# Sensor.net
KiCad netlist of a schematic drawn in Altium Designer
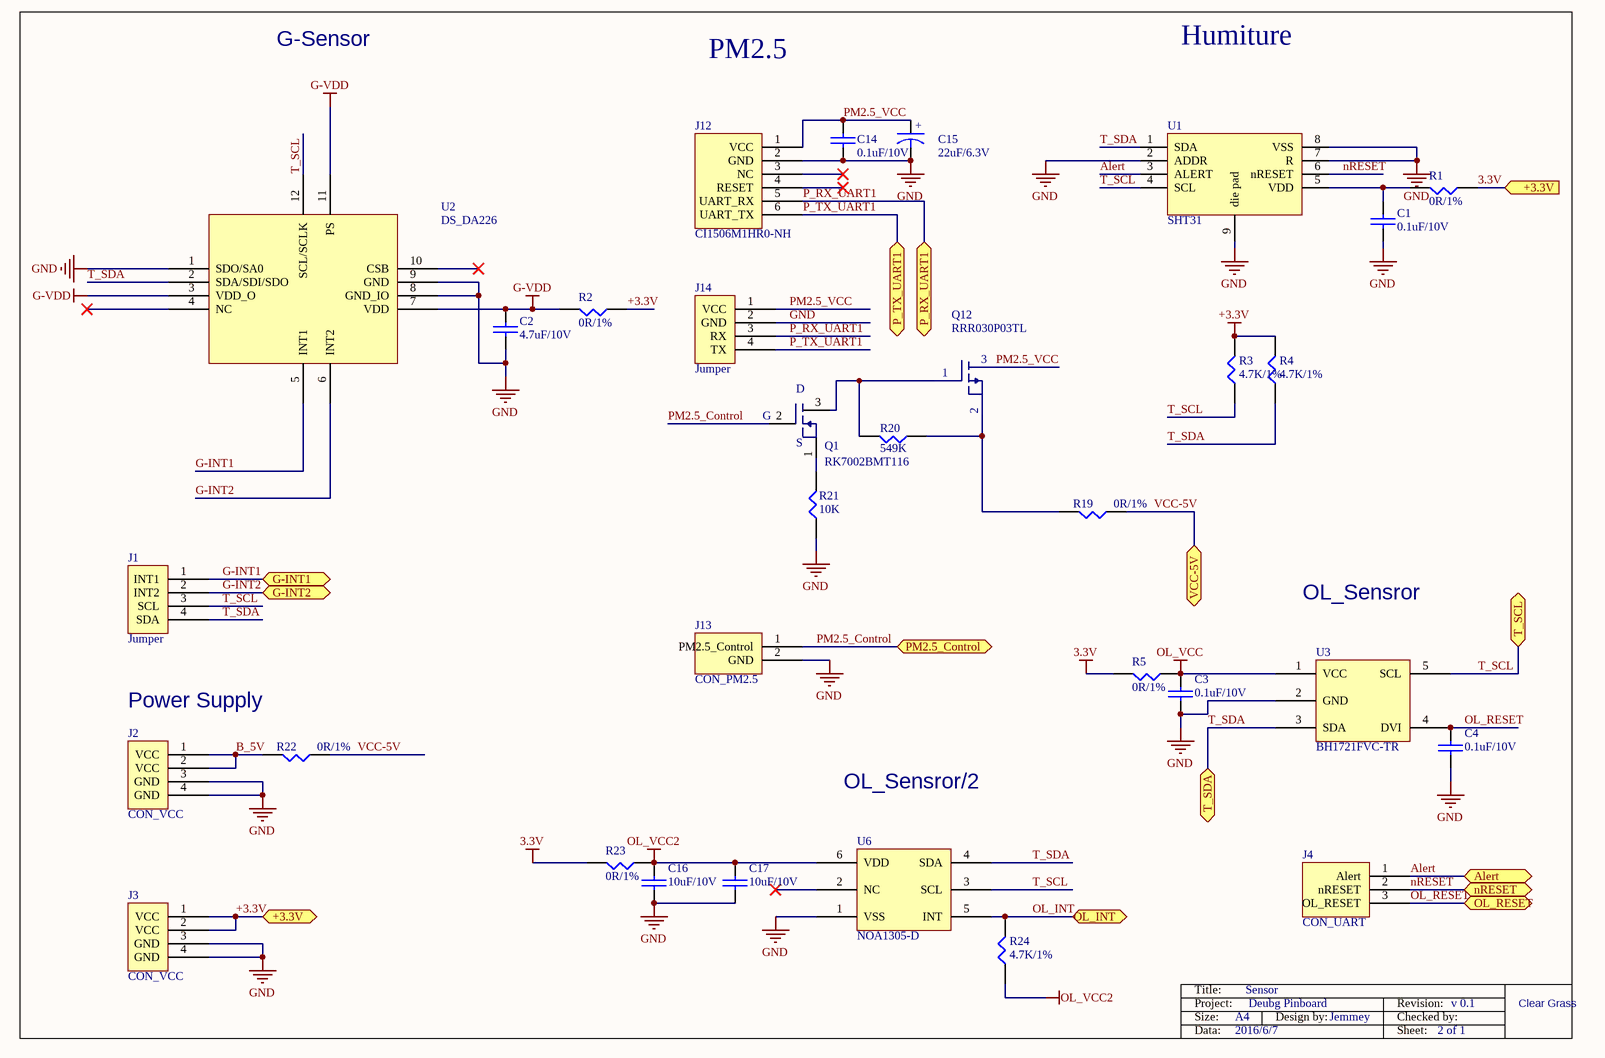
[diagram p0: Sensor.SchDoc]

(export (version "E")
  (design (tool "Eeschema 10.0.6"))
  (components
    (comp (ref "C1")
      (value "0.1uF/10V")
      (footprint "0402C")
      (description "厂家：Murata，型号：GRM155R71A104KA01D")
      (libsource (lib "*") (part "CAP"))
    )
    (comp (ref "C2")
      (value "4.7uF/10V")
      (footprint "0402C")
      (description "厂家：Murata，型号：GRM155R71A104KA01D")
      (libsource (lib "*") (part "CAP"))
    )
    (comp (ref "C3")
      (value "0.1uF/10V")
      (footprint "0402C")
      (description "厂家：Murata，型号：")
      (libsource (lib "*") (part "CAP"))
    )
    (comp (ref "C4")
      (value "0.1uF/10V")
      (footprint "0402C")
      (description "厂家：Murata，型号：")
      (libsource (lib "*") (part "CAP"))
    )
    (comp (ref "C14")
      (value "0.1uF/10V")
      (footprint "0402C")
      (description "厂家：Murata，型号：")
      (libsource (lib "*") (part "CAP"))
    )
    (comp (ref "C15")
      (value "22uF/6.3V")
      (footprint "3216")
      (description "厂家：ROHM，型号：TAJC227K010RNJ")
      (libsource (lib "MoJi LIB") (part "Capacitor"))
    )
    (comp (ref "C16")
      (value "10uF/10V")
      (footprint "0603C")
      (description "厂家：Murata，型号：")
      (libsource (lib "*") (part "CAP"))
    )
    (comp (ref "C17")
      (value "10uF/10V")
      (footprint "0603C")
      (description "厂家：Murata，型号：")
      (libsource (lib "*") (part "CAP"))
    )
    (comp (ref "J1")
      (value "Jumper")
      (footprint "2.54*4")
      (libsource (lib "Debug Pinborad_1") (part "Jumper*4"))
    )
    (comp (ref "J2")
      (value "CON_VCC")
      (footprint "2.54*4")
      (libsource (lib "Debug Pinborad_1") (part "CON_VCC"))
    )
    (comp (ref "J3")
      (value "CON_VCC")
      (footprint "2.54*4")
      (libsource (lib "Debug Pinborad_1") (part "CON_VCC"))
    )
    (comp (ref "J4")
      (value "CON_UART")
      (footprint "2.54*3")
      (libsource (lib "Debug Pinborad") (part "CON_UART"))
    )
    (comp (ref "J12")
      (value "CI1506M1HR0-NH")
      (footprint "WTB_SIDE_6PIN")
      (description "厂家：瀚荃股份，型号：CI1506M1HR0-NH")
      (libsource (lib "Bran PinBoard") (part "CI1506M1HR0-NH"))
    )
    (comp (ref "J13")
      (value "CON_PM2.5")
      (footprint "2.54*2")
      (libsource (lib "Bran PinBoard") (part "CON_PM2.5"))
    )
    (comp (ref "J14")
      (value "Jumper")
      (footprint "2.54*4")
      (libsource (lib "Bran PinBoard") (part "Jumper*4*PM25"))
    )
    (comp (ref "Q1")
      (value "RK7002BMT116")
      (footprint "SOT23")
      (description "厂家：ROHM，型号：RK7002BMT116")
      (libsource (lib "Amber") (part "RK7002BMT116"))
    )
    (comp (ref "Q12")
      (value "RRR030P03TL")
      (footprint "TSMT3")
      (description "厂家：ROHM，型号：RRR030P03TL")
      (libsource (lib "*") (part "PMOS"))
    )
    (comp (ref "R1")
      (value "0R/1%")
      (footprint "0603R")
      (description "厂家：Yageo，型号：RC0402FR-0710KL")
      (libsource (lib "*") (part "RES1"))
    )
    (comp (ref "R2")
      (value "0R/1%")
      (footprint "0603R")
      (description "厂家：Yageo，型号：RC0402FR-0710KL")
      (libsource (lib "*") (part "RES1"))
    )
    (comp (ref "R3")
      (value "4.7K/1%")
      (footprint "0402R")
      (description "厂家：Yageo，型号：RC0402FR-0710KL")
      (libsource (lib "*") (part "RES1"))
    )
    (comp (ref "R4")
      (value "4.7K/1%")
      (footprint "0402R")
      (description "厂家：Yageo，型号：RC0402FR-0710KL")
      (libsource (lib "*") (part "RES1"))
    )
    (comp (ref "R5")
      (value "0R/1%")
      (footprint "0603R")
      (description "厂家：Yageo，型号：RC0402FR-0710KL")
      (libsource (lib "*") (part "RES1"))
    )
    (comp (ref "R19")
      (value "0R/1%")
      (footprint "0603R")
      (description "厂家：Yageo，型号：RC0402FR-070RL")
      (libsource (lib "*") (part "RES1"))
    )
    (comp (ref "R20") (value "549K") (footprint "0402R") (libsource (lib "*") (part "RES1")))
    (comp (ref "R21") (value "10K") (footprint "0402R") (libsource (lib "*") (part "RES1")))
    (comp (ref "R22")
      (value "0R/1%")
      (footprint "0603R")
      (description "厂家：Yageo，型号：RC0402FR-070RL")
      (libsource (lib "*") (part "RES1"))
    )
    (comp (ref "R23")
      (value "0R/1%")
      (footprint "0603R")
      (description "厂家：Yageo，型号：RC0402FR-0710KL")
      (libsource (lib "*") (part "RES1"))
    )
    (comp (ref "R24")
      (value "4.7K/1%")
      (footprint "0402R")
      (description "厂家：Yageo，型号：RC0402FR-0710KL")
      (libsource (lib "*") (part "RES1"))
    )
    (comp (ref "U1")
      (value "SHT31")
      (footprint "DFN")
      (description "厂家：盛思睿，型号：SHT31")
      (libsource (lib "Temp Sensirion assy FPC") (part "SHT31"))
    )
    (comp (ref "U2")
      (value "DS_DA226")
      (footprint "LGA-12")
      (description "厂家：ST，型号：LIS2DH12")
      (libsource (lib "Debug Pinborad") (part "LIS2DE12"))
    )
    (comp (ref "U3")
      (value "BH1721FVC-TR")
      (footprint "WSOF5")
      (libsource (lib "Schlib1") (part "BH1721FVC-TR"))
    )
    (comp (ref "U6")
      (value "NOA1305-D")
      (footprint "CUDFN6")
      (libsource (lib "Bran PinBoard") (part "NOA1305-D"))
    )
  )
  (nets
    (net (code "1") (name "+3.3V") (class "Default")
      (node (ref "J3") (pin "1") (pinfunction "VCC_1") (pintype "passive"))
      (node (ref "J3") (pin "2") (pinfunction "VCC_2") (pintype "passive"))
      (node (ref "R1") (pin "1") (pinfunction "1_1") (pintype "passive"))
      (node (ref "R2") (pin "1") (pinfunction "1_1") (pintype "passive"))
      (node (ref "R23") (pin "2") (pinfunction "2_2") (pintype "passive"))
      (node (ref "R3") (pin "2") (pinfunction "2_2") (pintype "passive"))
      (node (ref "R4") (pin "2") (pinfunction "2_2") (pintype "passive"))
      (node (ref "R5") (pin "2") (pinfunction "2_2") (pintype "passive"))
    )
    (net (code "2") (name "/Alert") (class "Default")
      (node (ref "J4") (pin "1") (pinfunction "Alert_1") (pintype "passive"))
      (node (ref "U1") (pin "3") (pinfunction "ALERT_3") (pintype "passive"))
    )
    (net (code "3") (name "/B_5V") (class "Default")
      (node (ref "J2") (pin "1") (pinfunction "VCC_1") (pintype "passive"))
      (node (ref "J2") (pin "2") (pinfunction "VCC_2") (pintype "passive"))
      (node (ref "R22") (pin "2") (pinfunction "2_2") (pintype "passive"))
    )
    (net (code "4") (name "/G-INT1") (class "Default")
      (node (ref "J1") (pin "1") (pinfunction "INT1_1") (pintype "passive"))
      (node (ref "U2") (pin "5") (pinfunction "INT1_5") (pintype "passive"))
    )
    (net (code "5") (name "/G-INT2") (class "Default")
      (node (ref "J1") (pin "2") (pinfunction "INT2_2") (pintype "passive"))
      (node (ref "U2") (pin "6") (pinfunction "INT2_6") (pintype "passive"))
    )
    (net (code "6") (name "/OL_INT") (class "Default")
      (node (ref "R24") (pin "2") (pinfunction "2_2") (pintype "passive"))
      (node (ref "U6") (pin "5") (pinfunction "INT_5") (pintype "passive"))
    )
    (net (code "7") (name "/OL_RESET") (class "Default")
      (node (ref "C4") (pin "1") (pinfunction "1_1") (pintype "passive"))
      (node (ref "J4") (pin "3") (pinfunction "OL_RESET_3") (pintype "passive"))
      (node (ref "U3") (pin "4") (pinfunction "DVI_4") (pintype "passive"))
    )
    (net (code "8") (name "/PM2.5_Control") (class "Default")
      (node (ref "J13") (pin "1") (pinfunction "PM2.5_Control_1") (pintype "passive"))
      (node (ref "Q1") (pin "2") (pinfunction "G_2") (pintype "passive"))
    )
    (net (code "9") (name "/PM2.5_VCC") (class "Default")
      (node (ref "C14") (pin "1") (pinfunction "1_1") (pintype "passive"))
      (node (ref "C15") (pin "1") (pinfunction "1_1") (pintype "passive"))
      (node (ref "J12") (pin "1") (pinfunction "VCC_1") (pintype "passive"))
      (node (ref "J14") (pin "1") (pinfunction "VCC_1") (pintype "passive"))
      (node (ref "Q12") (pin "3") (pinfunction "D_3") (pintype "passive"))
    )
    (net (code "10") (name "/P_RX_UART1") (class "Default")
      (node (ref "J12") (pin "5") (pinfunction "UART_RX_5") (pintype "passive"))
      (node (ref "J14") (pin "3") (pinfunction "RX_3") (pintype "passive"))
    )
    (net (code "11") (name "/P_TX_UART1") (class "Default")
      (node (ref "J12") (pin "6") (pinfunction "UART_TX_6") (pintype "passive"))
      (node (ref "J14") (pin "4") (pinfunction "TX_4") (pintype "passive"))
    )
    (net (code "12") (name "/T_SCL") (class "Default")
      (node (ref "J1") (pin "3") (pinfunction "SCL_3") (pintype "passive"))
      (node (ref "R3") (pin "1") (pinfunction "1_1") (pintype "passive"))
      (node (ref "U1") (pin "4") (pinfunction "SCL_4") (pintype "passive"))
      (node (ref "U2") (pin "12") (pinfunction "SCL/SCLK_12") (pintype "passive"))
      (node (ref "U3") (pin "5") (pinfunction "SCL_5") (pintype "passive"))
      (node (ref "U6") (pin "3") (pinfunction "SCL_3") (pintype "passive"))
    )
    (net (code "13") (name "/T_SDA") (class "Default")
      (node (ref "J1") (pin "4") (pinfunction "SDA_4") (pintype "passive"))
      (node (ref "R4") (pin "1") (pinfunction "1_1") (pintype "passive"))
      (node (ref "U1") (pin "1") (pinfunction "SDA_1") (pintype "passive"))
      (node (ref "U2") (pin "2") (pinfunction "SDA/SDI/SDO_2") (pintype "passive"))
      (node (ref "U3") (pin "3") (pinfunction "SDA_3") (pintype "passive"))
      (node (ref "U6") (pin "4") (pinfunction "SDA_4") (pintype "passive"))
    )
    (net (code "14") (name "/VCC-5V") (class "Default")
      (node (ref "R19") (pin "1") (pinfunction "1_1") (pintype "passive"))
      (node (ref "R22") (pin "1") (pinfunction "1_1") (pintype "passive"))
    )
    (net (code "15") (name "/nRESET") (class "Default")
      (node (ref "J4") (pin "2") (pinfunction "nRESET_2") (pintype "passive"))
      (node (ref "U1") (pin "6") (pinfunction "nRESET_6") (pintype "passive"))
    )
    (net (code "16") (name "G-VDD") (class "Default")
      (node (ref "C2") (pin "1") (pinfunction "1_1") (pintype "passive"))
      (node (ref "R2") (pin "2") (pinfunction "2_2") (pintype "passive"))
      (node (ref "U2") (pin "11") (pinfunction "PS_11") (pintype "passive"))
      (node (ref "U2") (pin "3") (pinfunction "VDD_O_3") (pintype "passive"))
      (node (ref "U2") (pin "7") (pinfunction "VDD_7") (pintype "passive"))
    )
    (net (code "17") (name "GND") (class "Default")
      (node (ref "C1") (pin "2") (pinfunction "2_2") (pintype "passive"))
      (node (ref "C14") (pin "2") (pinfunction "2_2") (pintype "passive"))
      (node (ref "C15") (pin "2") (pinfunction "2_2") (pintype "passive"))
      (node (ref "C16") (pin "2") (pinfunction "2_2") (pintype "passive"))
      (node (ref "C17") (pin "2") (pinfunction "2_2") (pintype "passive"))
      (node (ref "C2") (pin "2") (pinfunction "2_2") (pintype "passive"))
      (node (ref "C3") (pin "2") (pinfunction "2_2") (pintype "passive"))
      (node (ref "C4") (pin "2") (pinfunction "2_2") (pintype "passive"))
      (node (ref "J12") (pin "2") (pinfunction "GND_2") (pintype "passive"))
      (node (ref "J13") (pin "2") (pinfunction "GND_2") (pintype "passive"))
      (node (ref "J14") (pin "2") (pinfunction "GND_2") (pintype "passive"))
      (node (ref "J2") (pin "3") (pinfunction "GND_3") (pintype "passive"))
      (node (ref "J2") (pin "4") (pinfunction "GND_4") (pintype "passive"))
      (node (ref "J3") (pin "3") (pinfunction "GND_3") (pintype "passive"))
      (node (ref "J3") (pin "4") (pinfunction "GND_4") (pintype "passive"))
      (node (ref "R21") (pin "1") (pinfunction "1_1") (pintype "passive"))
      (node (ref "U1") (pin "2") (pinfunction "ADDR_2") (pintype "passive"))
      (node (ref "U1") (pin "7") (pinfunction "R_7") (pintype "passive"))
      (node (ref "U1") (pin "8") (pinfunction "VSS_8") (pintype "passive"))
      (node (ref "U1") (pin "9") (pinfunction "die_pad_9") (pintype "passive"))
      (node (ref "U2") (pin "1") (pinfunction "SDO/SA0_1") (pintype "passive"))
      (node (ref "U2") (pin "8") (pinfunction "GND_IO_8") (pintype "passive"))
      (node (ref "U2") (pin "9") (pinfunction "GND_9") (pintype "passive"))
      (node (ref "U3") (pin "2") (pinfunction "GND_2") (pintype "passive"))
      (node (ref "U6") (pin "1") (pinfunction "VSS_1") (pintype "passive"))
    )
    (net (code "18") (name "Net-(Q1-D)") (class "Default")
      (node (ref "Q1") (pin "3") (pinfunction "D_3") (pintype "passive"))
      (node (ref "Q12") (pin "1") (pinfunction "G_1") (pintype "passive"))
      (node (ref "R20") (pin "2") (pinfunction "2_2") (pintype "passive"))
    )
    (net (code "19") (name "Net-(Q1-S)") (class "Default")
      (node (ref "Q1") (pin "1") (pinfunction "S_1") (pintype "passive"))
      (node (ref "R21") (pin "2") (pinfunction "2_2") (pintype "passive"))
    )
    (net (code "20") (name "Net-(Q12-S)") (class "Default")
      (node (ref "Q12") (pin "2") (pinfunction "S_2") (pintype "passive"))
      (node (ref "R19") (pin "2") (pinfunction "2_2") (pintype "passive"))
      (node (ref "R20") (pin "1") (pinfunction "1_1") (pintype "passive"))
    )
    (net (code "21") (name "Net-(U1-VDD)") (class "Default")
      (node (ref "C1") (pin "1") (pinfunction "1_1") (pintype "passive"))
      (node (ref "R1") (pin "2") (pinfunction "2_2") (pintype "passive"))
      (node (ref "U1") (pin "5") (pinfunction "VDD_5") (pintype "passive"))
    )
    (net (code "22") (name "OL_VCC") (class "Default")
      (node (ref "C3") (pin "1") (pinfunction "1_1") (pintype "passive"))
      (node (ref "R5") (pin "1") (pinfunction "1_1") (pintype "passive"))
      (node (ref "U3") (pin "1") (pinfunction "VCC_1") (pintype "passive"))
    )
    (net (code "23") (name "OL_VCC2") (class "Default")
      (node (ref "C16") (pin "1") (pinfunction "1_1") (pintype "passive"))
      (node (ref "C17") (pin "1") (pinfunction "1_1") (pintype "passive"))
      (node (ref "R23") (pin "1") (pinfunction "1_1") (pintype "passive"))
      (node (ref "R24") (pin "1") (pinfunction "1_1") (pintype "passive"))
      (node (ref "U6") (pin "6") (pinfunction "VDD_6") (pintype "passive"))
    )
    (net (code "24") (name "unconnected-(J12-NC-Pad3)") (class "Default")
      (node (ref "J12") (pin "3") (pinfunction "NC_3") (pintype "passive+no_connect"))
    )
    (net (code "25") (name "unconnected-(J12-RESET-Pad4)") (class "Default")
      (node (ref "J12") (pin "4") (pinfunction "RESET_4") (pintype "passive+no_connect"))
    )
    (net (code "26") (name "unconnected-(U2-CSB-Pad10)") (class "Default")
      (node (ref "U2") (pin "10") (pinfunction "CSB_10") (pintype "passive+no_connect"))
    )
    (net (code "27") (name "unconnected-(U2-NC-Pad4)") (class "Default")
      (node (ref "U2") (pin "4") (pinfunction "NC_4") (pintype "passive+no_connect"))
    )
    (net (code "28") (name "unconnected-(U6-NC-Pad2)") (class "Default")
      (node (ref "U6") (pin "2") (pinfunction "NC_2") (pintype "passive+no_connect"))
    )
  )
)
